# M3.net
KiCad netlist of a schematic drawn in EAGLE
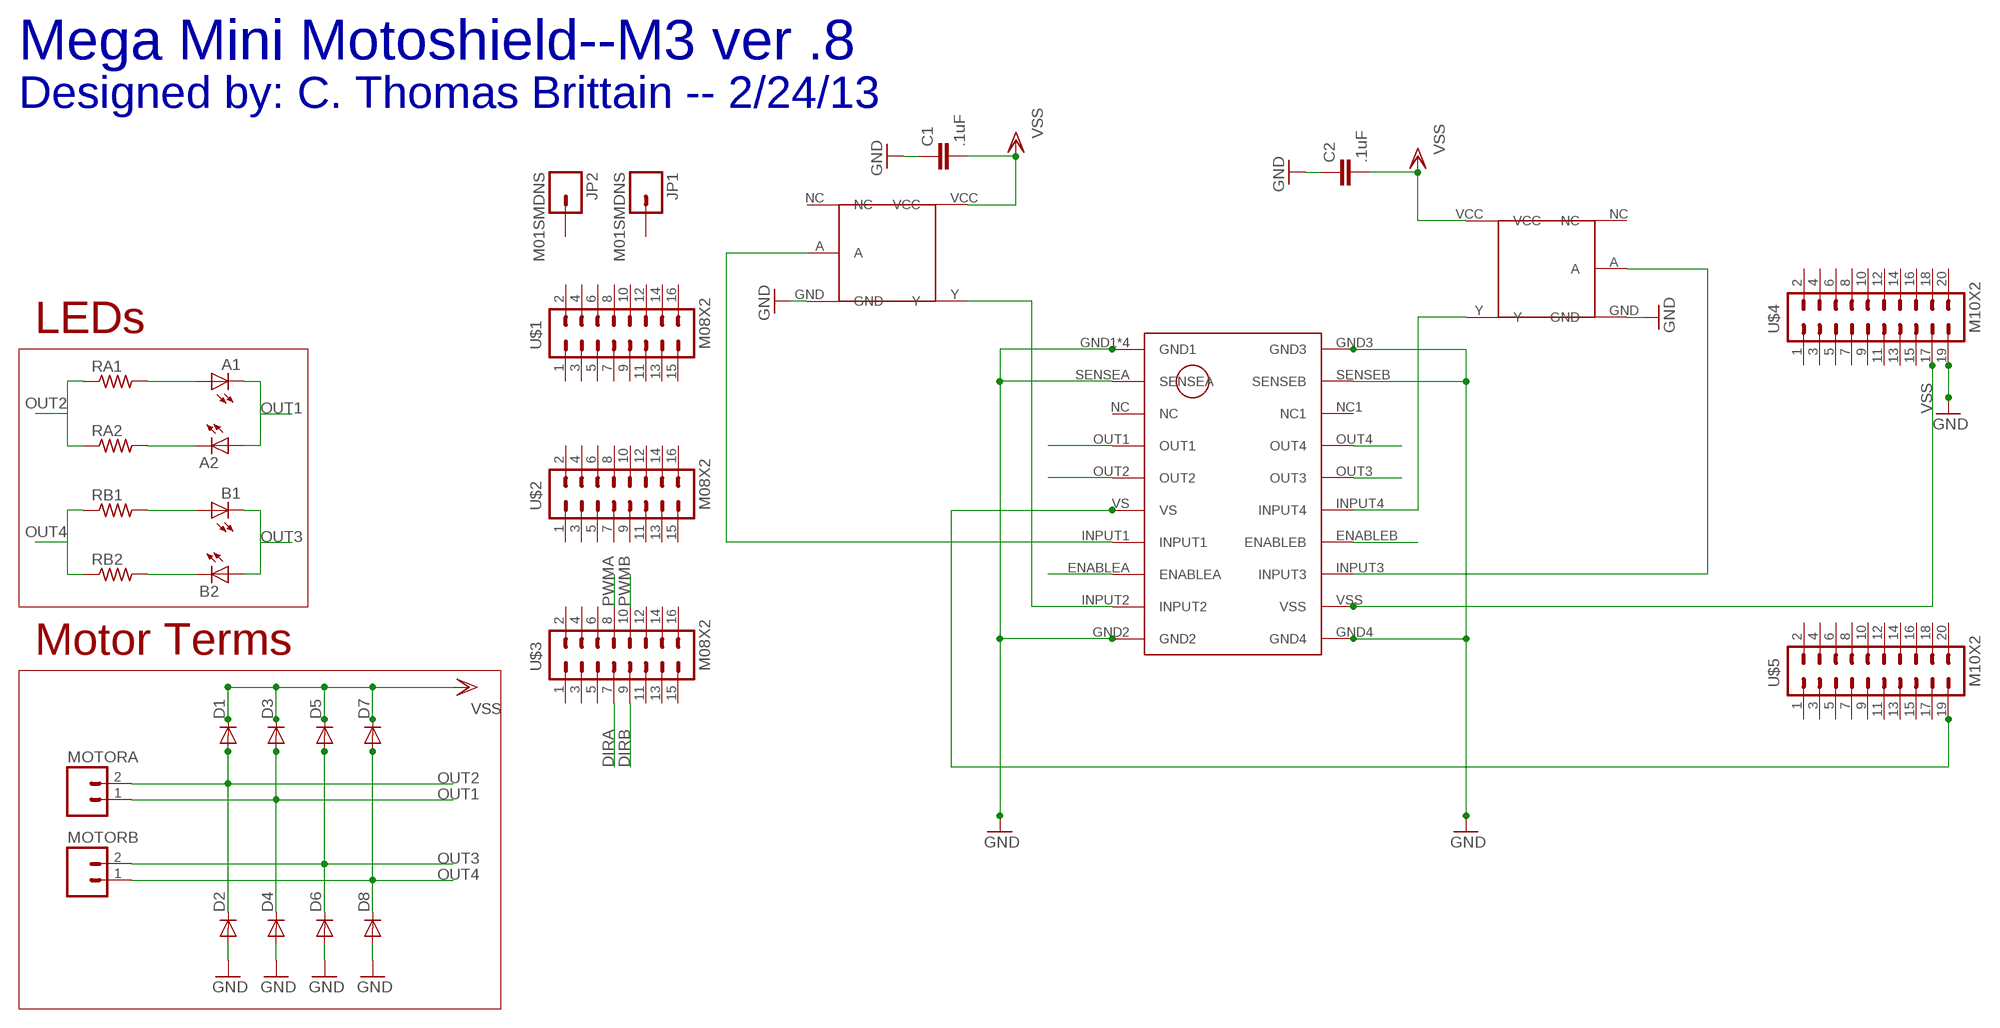
[diagram p0: schematic, sheet 1]

(export (version "E")
  (design (tool "Eeschema 10.0.6"))
  (components
    (comp (ref "A1")
      (value "LEDSML0603")
      (footprint "eagle-import:SML0603")
      (libsource (lib "eagle-import") (part "LEDSML0603"))
    )
    (comp (ref "A2")
      (value "LEDSML0603")
      (footprint "eagle-import:SML0603")
      (libsource (lib "eagle-import") (part "LEDSML0603"))
    )
    (comp (ref "B1")
      (value "LEDSML0603")
      (footprint "eagle-import:SML0603")
      (libsource (lib "eagle-import") (part "LEDSML0603"))
    )
    (comp (ref "B2")
      (value "LEDSML0603")
      (footprint "eagle-import:SML0603")
      (libsource (lib "eagle-import") (part "LEDSML0603"))
    )
    (comp (ref "C1")
      (value ".1uF")
      (footprint "eagle-import:C0805")
      (libsource (lib "eagle-import") (part "C-EUC0805"))
    )
    (comp (ref "C2")
      (value ".1uF")
      (footprint "eagle-import:C0805")
      (libsource (lib "eagle-import") (part "C-EUC0805"))
    )
    (comp (ref "D1")
      (value "DIODESMA")
      (footprint "eagle-import:SMA-DIODE")
      (libsource (lib "eagle-import") (part "DIODESMA"))
    )
    (comp (ref "D2")
      (value "DIODESMA")
      (footprint "eagle-import:SMA-DIODE")
      (libsource (lib "eagle-import") (part "DIODESMA"))
    )
    (comp (ref "D3")
      (value "DIODESMA")
      (footprint "eagle-import:SMA-DIODE")
      (libsource (lib "eagle-import") (part "DIODESMA"))
    )
    (comp (ref "D4")
      (value "DIODESMA")
      (footprint "eagle-import:SMA-DIODE")
      (libsource (lib "eagle-import") (part "DIODESMA"))
    )
    (comp (ref "D5")
      (value "DIODESMA")
      (footprint "eagle-import:SMA-DIODE")
      (libsource (lib "eagle-import") (part "DIODESMA"))
    )
    (comp (ref "D6")
      (value "DIODESMA")
      (footprint "eagle-import:SMA-DIODE")
      (libsource (lib "eagle-import") (part "DIODESMA"))
    )
    (comp (ref "D7")
      (value "DIODESMA")
      (footprint "eagle-import:SMA-DIODE")
      (libsource (lib "eagle-import") (part "DIODESMA"))
    )
    (comp (ref "D8")
      (value "DIODESMA")
      (footprint "eagle-import:SMA-DIODE")
      (libsource (lib "eagle-import") (part "DIODESMA"))
    )
    (comp (ref "JP1")
      (value "M01SMDNS")
      (footprint "eagle-import:1X01NS")
      (libsource (lib "eagle-import") (part "M01SMDNS"))
    )
    (comp (ref "JP2")
      (value "M01SMDNS")
      (footprint "eagle-import:1X01NS")
      (libsource (lib "eagle-import") (part "M01SMDNS"))
    )
    (comp (ref "MOTORA")
      (value "M023.5MM")
      (footprint "eagle-import:SCREWTERMINAL-3.5MM-2")
      (libsource (lib "eagle-import") (part "M023.5MM"))
    )
    (comp (ref "MOTORB")
      (value "M023.5MM")
      (footprint "eagle-import:SCREWTERMINAL-3.5MM-2")
      (libsource (lib "eagle-import") (part "M023.5MM"))
    )
    (comp (ref "RA1")
      (value "R-US_R0805")
      (footprint "eagle-import:R0805")
      (libsource (lib "eagle-import") (part "R-US_R0805"))
    )
    (comp (ref "RA2")
      (value "R-US_R0805")
      (footprint "eagle-import:R0805")
      (libsource (lib "eagle-import") (part "R-US_R0805"))
    )
    (comp (ref "RB1")
      (value "R-US_R0805")
      (footprint "eagle-import:R0805")
      (libsource (lib "eagle-import") (part "R-US_R0805"))
    )
    (comp (ref "RB2")
      (value "R-US_R0805")
      (footprint "eagle-import:R0805")
      (libsource (lib "eagle-import") (part "R-US_R0805"))
    )
    (comp (ref "U$1")
      (value "M08X2")
      (footprint "eagle-import:2X8")
      (libsource (lib "eagle-import") (part "M08X2"))
    )
    (comp (ref "U$2")
      (value "M08X2")
      (footprint "eagle-import:2X8")
      (libsource (lib "eagle-import") (part "M08X2"))
    )
    (comp (ref "U$3")
      (value "M08X2")
      (footprint "eagle-import:2X8")
      (libsource (lib "eagle-import") (part "M08X2"))
    )
    (comp (ref "U$4")
      (value "M10X2")
      (footprint "eagle-import:2X10")
      (libsource (lib "eagle-import") (part "M10X2"))
    )
    (comp (ref "U$5")
      (value "M10X2")
      (footprint "eagle-import:2X10")
      (libsource (lib "eagle-import") (part "M10X2"))
    )
    (comp (ref "U$6")
      (value "L298P")
      (footprint "eagle-import:SMARTPRJ_POWER-SO20")
      (libsource (lib "eagle-import") (part "L298P"))
    )
    (comp (ref "U$7")
      (value "74HC1G04")
      (footprint "eagle-import:SPARKFUN_SC70")
      (libsource (lib "eagle-import") (part "74HC1G04"))
    )
    (comp (ref "U$8")
      (value "74HC1G04")
      (footprint "eagle-import:SPARKFUN_SC70")
      (libsource (lib "eagle-import") (part "74HC1G04"))
    )
  )
  (nets
    (net (code "1") (name "/DIRA") (class "Default")
      (node (ref "U$3") (pin "7") (pinfunction "7_7") (pintype "passive"))
      (node (ref "U$6") (pin "INPUT1") (pinfunction "INPUT1_INPUT1") (pintype "bidirectional"))
      (node (ref "U$7") (pin "A") (pinfunction "A_A") (pintype "bidirectional"))
    )
    (net (code "2") (name "/DIRB") (class "Default")
      (node (ref "U$3") (pin "9") (pinfunction "9_9") (pintype "passive"))
      (node (ref "U$6") (pin "INPUT3") (pinfunction "INPUT3_INPUT3") (pintype "bidirectional"))
      (node (ref "U$8") (pin "A") (pinfunction "A_A") (pintype "bidirectional"))
    )
    (net (code "3") (name "/OUT1") (class "Default")
      (node (ref "A1") (pin "C") (pinfunction "C_C") (pintype "passive"))
      (node (ref "A2") (pin "A") (pinfunction "A_A") (pintype "passive"))
      (node (ref "D3") (pin "A") (pinfunction "A_A") (pintype "passive"))
      (node (ref "D4") (pin "C") (pinfunction "C_C") (pintype "passive"))
      (node (ref "MOTORA") (pin "1") (pinfunction "1_1") (pintype "passive"))
      (node (ref "U$6") (pin "OUT1") (pinfunction "OUT1_OUT1") (pintype "bidirectional"))
    )
    (net (code "4") (name "/OUT2") (class "Default")
      (node (ref "D1") (pin "A") (pinfunction "A_A") (pintype "passive"))
      (node (ref "D2") (pin "C") (pinfunction "C_C") (pintype "passive"))
      (node (ref "MOTORA") (pin "2") (pinfunction "2_2") (pintype "passive"))
      (node (ref "RA1") (pin "1") (pinfunction "1_1") (pintype "passive"))
      (node (ref "RA2") (pin "1") (pinfunction "1_1") (pintype "passive"))
      (node (ref "U$6") (pin "OUT2") (pinfunction "OUT2_OUT2") (pintype "bidirectional"))
    )
    (net (code "5") (name "/OUT3") (class "Default")
      (node (ref "B1") (pin "C") (pinfunction "C_C") (pintype "passive"))
      (node (ref "B2") (pin "A") (pinfunction "A_A") (pintype "passive"))
      (node (ref "D5") (pin "A") (pinfunction "A_A") (pintype "passive"))
      (node (ref "D6") (pin "C") (pinfunction "C_C") (pintype "passive"))
      (node (ref "MOTORB") (pin "2") (pinfunction "2_2") (pintype "passive"))
      (node (ref "U$6") (pin "OUT4") (pinfunction "OUT4_OUT4") (pintype "bidirectional"))
    )
    (net (code "6") (name "/OUT4") (class "Default")
      (node (ref "D7") (pin "A") (pinfunction "A_A") (pintype "passive"))
      (node (ref "D8") (pin "C") (pinfunction "C_C") (pintype "passive"))
      (node (ref "MOTORB") (pin "1") (pinfunction "1_1") (pintype "passive"))
      (node (ref "RB1") (pin "1") (pinfunction "1_1") (pintype "passive"))
      (node (ref "RB2") (pin "1") (pinfunction "1_1") (pintype "passive"))
      (node (ref "U$6") (pin "OUT3") (pinfunction "OUT3_OUT3") (pintype "bidirectional"))
    )
    (net (code "7") (name "/PWMA") (class "Default")
      (node (ref "U$3") (pin "8") (pinfunction "8_8") (pintype "passive"))
      (node (ref "U$6") (pin "ENABLEA") (pinfunction "ENABLEA_ENABLEA") (pintype "bidirectional"))
    )
    (net (code "8") (name "/PWMB") (class "Default")
      (node (ref "U$3") (pin "10") (pinfunction "10_10") (pintype "passive"))
      (node (ref "U$6") (pin "ENABLEB") (pinfunction "ENABLEB_ENABLEB") (pintype "bidirectional"))
    )
    (net (code "9") (name "GND") (class "Default")
      (node (ref "C1") (pin "1") (pinfunction "1_1") (pintype "passive"))
      (node (ref "C2") (pin "1") (pinfunction "1_1") (pintype "passive"))
      (node (ref "D2") (pin "A") (pinfunction "A_A") (pintype "passive"))
      (node (ref "D4") (pin "A") (pinfunction "A_A") (pintype "passive"))
      (node (ref "D6") (pin "A") (pinfunction "A_A") (pintype "passive"))
      (node (ref "D8") (pin "A") (pinfunction "A_A") (pintype "passive"))
      (node (ref "U$4") (pin "19") (pinfunction "19_19") (pintype "passive"))
      (node (ref "U$6") (pin "GND1") (pinfunction "GND1_GND1") (pintype "bidirectional"))
      (node (ref "U$6") (pin "GND2") (pinfunction "GND2_GND2") (pintype "bidirectional"))
      (node (ref "U$6") (pin "GND3") (pinfunction "GND3_GND3") (pintype "bidirectional"))
      (node (ref "U$6") (pin "GND4") (pinfunction "GND4_GND4") (pintype "bidirectional"))
      (node (ref "U$6") (pin "GND5") (pinfunction "GND1_GND5") (pintype "bidirectional"))
      (node (ref "U$6") (pin "GND6") (pinfunction "GND1_GND6") (pintype "bidirectional"))
      (node (ref "U$6") (pin "GND7") (pinfunction "GND1_GND7") (pintype "bidirectional"))
      (node (ref "U$6") (pin "SENSEA") (pinfunction "SENSEA_SENSEA") (pintype "bidirectional"))
      (node (ref "U$6") (pin "SENSEB") (pinfunction "SENSEB_SENSEB") (pintype "bidirectional"))
      (node (ref "U$7") (pin "GND") (pinfunction "GND_GND") (pintype "bidirectional"))
      (node (ref "U$8") (pin "GND") (pinfunction "GND_GND") (pintype "bidirectional"))
    )
    (net (code "10") (name "Net-(A1-PadA)") (class "Default")
      (node (ref "A1") (pin "A") (pinfunction "A_A") (pintype "passive"))
      (node (ref "RA1") (pin "2") (pinfunction "2_2") (pintype "passive"))
    )
    (net (code "11") (name "Net-(A2-PadC)") (class "Default")
      (node (ref "A2") (pin "C") (pinfunction "C_C") (pintype "passive"))
      (node (ref "RA2") (pin "2") (pinfunction "2_2") (pintype "passive"))
    )
    (net (code "12") (name "Net-(B1-PadA)") (class "Default")
      (node (ref "B1") (pin "A") (pinfunction "A_A") (pintype "passive"))
      (node (ref "RB1") (pin "2") (pinfunction "2_2") (pintype "passive"))
    )
    (net (code "13") (name "Net-(B2-PadC)") (class "Default")
      (node (ref "B2") (pin "C") (pinfunction "C_C") (pintype "passive"))
      (node (ref "RB2") (pin "2") (pinfunction "2_2") (pintype "passive"))
    )
    (net (code "14") (name "Net-(U$5-Pad19)") (class "Default")
      (node (ref "U$5") (pin "19") (pinfunction "19_19") (pintype "passive"))
      (node (ref "U$6") (pin "VS") (pinfunction "VS_VS") (pintype "bidirectional"))
    )
    (net (code "15") (name "Net-(U$6-PadINPUT2)") (class "Default")
      (node (ref "U$6") (pin "INPUT2") (pinfunction "INPUT2_INPUT2") (pintype "bidirectional"))
      (node (ref "U$7") (pin "Y") (pinfunction "Y_Y") (pintype "bidirectional"))
    )
    (net (code "16") (name "Net-(U$6-PadINPUT4)") (class "Default")
      (node (ref "U$6") (pin "INPUT4") (pinfunction "INPUT4_INPUT4") (pintype "bidirectional"))
      (node (ref "U$8") (pin "Y") (pinfunction "Y_Y") (pintype "bidirectional"))
    )
    (net (code "17") (name "VSS") (class "Default")
      (node (ref "C1") (pin "2") (pinfunction "2_2") (pintype "passive"))
      (node (ref "C2") (pin "2") (pinfunction "2_2") (pintype "passive"))
      (node (ref "D1") (pin "C") (pinfunction "C_C") (pintype "passive"))
      (node (ref "D3") (pin "C") (pinfunction "C_C") (pintype "passive"))
      (node (ref "D5") (pin "C") (pinfunction "C_C") (pintype "passive"))
      (node (ref "D7") (pin "C") (pinfunction "C_C") (pintype "passive"))
      (node (ref "U$4") (pin "17") (pinfunction "17_17") (pintype "passive"))
      (node (ref "U$6") (pin "VSS") (pinfunction "VSS_VSS") (pintype "bidirectional"))
      (node (ref "U$7") (pin "VCC") (pinfunction "VCC_VCC") (pintype "bidirectional"))
      (node (ref "U$8") (pin "VCC") (pinfunction "VCC_VCC") (pintype "bidirectional"))
    )
    (net (code "18") (name "unconnected-(JP1-Pad1)") (class "Default")
      (node (ref "JP1") (pin "1") (pinfunction "1_1") (pintype "passive"))
    )
    (net (code "19") (name "unconnected-(JP2-Pad1)") (class "Default")
      (node (ref "JP2") (pin "1") (pinfunction "1_1") (pintype "passive"))
    )
    (net (code "20") (name "unconnected-(U$1-Pad1)") (class "Default")
      (node (ref "U$1") (pin "1") (pinfunction "1_1") (pintype "passive"))
    )
    (net (code "21") (name "unconnected-(U$1-Pad2)") (class "Default")
      (node (ref "U$1") (pin "2") (pinfunction "2_2") (pintype "passive"))
    )
    (net (code "22") (name "unconnected-(U$1-Pad3)") (class "Default")
      (node (ref "U$1") (pin "3") (pinfunction "3_3") (pintype "passive"))
    )
    (net (code "23") (name "unconnected-(U$1-Pad4)") (class "Default")
      (node (ref "U$1") (pin "4") (pinfunction "4_4") (pintype "passive"))
    )
    (net (code "24") (name "unconnected-(U$1-Pad5)") (class "Default")
      (node (ref "U$1") (pin "5") (pinfunction "5_5") (pintype "passive"))
    )
    (net (code "25") (name "unconnected-(U$1-Pad6)") (class "Default")
      (node (ref "U$1") (pin "6") (pinfunction "6_6") (pintype "passive"))
    )
    (net (code "26") (name "unconnected-(U$1-Pad7)") (class "Default")
      (node (ref "U$1") (pin "7") (pinfunction "7_7") (pintype "passive"))
    )
    (net (code "27") (name "unconnected-(U$1-Pad8)") (class "Default")
      (node (ref "U$1") (pin "8") (pinfunction "8_8") (pintype "passive"))
    )
    (net (code "28") (name "unconnected-(U$1-Pad9)") (class "Default")
      (node (ref "U$1") (pin "9") (pinfunction "9_9") (pintype "passive"))
    )
    (net (code "29") (name "unconnected-(U$1-Pad10)") (class "Default")
      (node (ref "U$1") (pin "10") (pinfunction "10_10") (pintype "passive"))
    )
    (net (code "30") (name "unconnected-(U$1-Pad11)") (class "Default")
      (node (ref "U$1") (pin "11") (pinfunction "11_11") (pintype "passive"))
    )
    (net (code "31") (name "unconnected-(U$1-Pad12)") (class "Default")
      (node (ref "U$1") (pin "12") (pinfunction "12_12") (pintype "passive"))
    )
    (net (code "32") (name "unconnected-(U$1-Pad13)") (class "Default")
      (node (ref "U$1") (pin "13") (pinfunction "13_13") (pintype "passive"))
    )
    (net (code "33") (name "unconnected-(U$1-Pad14)") (class "Default")
      (node (ref "U$1") (pin "14") (pinfunction "14_14") (pintype "passive"))
    )
    (net (code "34") (name "unconnected-(U$1-Pad15)") (class "Default")
      (node (ref "U$1") (pin "15") (pinfunction "15_15") (pintype "passive"))
    )
    (net (code "35") (name "unconnected-(U$1-Pad16)") (class "Default")
      (node (ref "U$1") (pin "16") (pinfunction "16_16") (pintype "passive"))
    )
    (net (code "36") (name "unconnected-(U$2-Pad1)") (class "Default")
      (node (ref "U$2") (pin "1") (pinfunction "1_1") (pintype "passive"))
    )
    (net (code "37") (name "unconnected-(U$2-Pad2)") (class "Default")
      (node (ref "U$2") (pin "2") (pinfunction "2_2") (pintype "passive"))
    )
    (net (code "38") (name "unconnected-(U$2-Pad3)") (class "Default")
      (node (ref "U$2") (pin "3") (pinfunction "3_3") (pintype "passive"))
    )
    (net (code "39") (name "unconnected-(U$2-Pad4)") (class "Default")
      (node (ref "U$2") (pin "4") (pinfunction "4_4") (pintype "passive"))
    )
    (net (code "40") (name "unconnected-(U$2-Pad5)") (class "Default")
      (node (ref "U$2") (pin "5") (pinfunction "5_5") (pintype "passive"))
    )
    (net (code "41") (name "unconnected-(U$2-Pad6)") (class "Default")
      (node (ref "U$2") (pin "6") (pinfunction "6_6") (pintype "passive"))
    )
    (net (code "42") (name "unconnected-(U$2-Pad7)") (class "Default")
      (node (ref "U$2") (pin "7") (pinfunction "7_7") (pintype "passive"))
    )
    (net (code "43") (name "unconnected-(U$2-Pad8)") (class "Default")
      (node (ref "U$2") (pin "8") (pinfunction "8_8") (pintype "passive"))
    )
    (net (code "44") (name "unconnected-(U$2-Pad9)") (class "Default")
      (node (ref "U$2") (pin "9") (pinfunction "9_9") (pintype "passive"))
    )
    (net (code "45") (name "unconnected-(U$2-Pad10)") (class "Default")
      (node (ref "U$2") (pin "10") (pinfunction "10_10") (pintype "passive"))
    )
    (net (code "46") (name "unconnected-(U$2-Pad11)") (class "Default")
      (node (ref "U$2") (pin "11") (pinfunction "11_11") (pintype "passive"))
    )
    (net (code "47") (name "unconnected-(U$2-Pad12)") (class "Default")
      (node (ref "U$2") (pin "12") (pinfunction "12_12") (pintype "passive"))
    )
    (net (code "48") (name "unconnected-(U$2-Pad13)") (class "Default")
      (node (ref "U$2") (pin "13") (pinfunction "13_13") (pintype "passive"))
    )
    (net (code "49") (name "unconnected-(U$2-Pad14)") (class "Default")
      (node (ref "U$2") (pin "14") (pinfunction "14_14") (pintype "passive"))
    )
    (net (code "50") (name "unconnected-(U$2-Pad15)") (class "Default")
      (node (ref "U$2") (pin "15") (pinfunction "15_15") (pintype "passive"))
    )
    (net (code "51") (name "unconnected-(U$2-Pad16)") (class "Default")
      (node (ref "U$2") (pin "16") (pinfunction "16_16") (pintype "passive"))
    )
    (net (code "52") (name "unconnected-(U$3-Pad1)") (class "Default")
      (node (ref "U$3") (pin "1") (pinfunction "1_1") (pintype "passive"))
    )
    (net (code "53") (name "unconnected-(U$3-Pad2)") (class "Default")
      (node (ref "U$3") (pin "2") (pinfunction "2_2") (pintype "passive"))
    )
    (net (code "54") (name "unconnected-(U$3-Pad3)") (class "Default")
      (node (ref "U$3") (pin "3") (pinfunction "3_3") (pintype "passive"))
    )
    (net (code "55") (name "unconnected-(U$3-Pad4)") (class "Default")
      (node (ref "U$3") (pin "4") (pinfunction "4_4") (pintype "passive"))
    )
    (net (code "56") (name "unconnected-(U$3-Pad5)") (class "Default")
      (node (ref "U$3") (pin "5") (pinfunction "5_5") (pintype "passive"))
    )
    (net (code "57") (name "unconnected-(U$3-Pad6)") (class "Default")
      (node (ref "U$3") (pin "6") (pinfunction "6_6") (pintype "passive"))
    )
    (net (code "58") (name "unconnected-(U$3-Pad11)") (class "Default")
      (node (ref "U$3") (pin "11") (pinfunction "11_11") (pintype "passive"))
    )
    (net (code "59") (name "unconnected-(U$3-Pad12)") (class "Default")
      (node (ref "U$3") (pin "12") (pinfunction "12_12") (pintype "passive"))
    )
    (net (code "60") (name "unconnected-(U$3-Pad13)") (class "Default")
      (node (ref "U$3") (pin "13") (pinfunction "13_13") (pintype "passive"))
    )
    (net (code "61") (name "unconnected-(U$3-Pad14)") (class "Default")
      (node (ref "U$3") (pin "14") (pinfunction "14_14") (pintype "passive"))
    )
    (net (code "62") (name "unconnected-(U$3-Pad15)") (class "Default")
      (node (ref "U$3") (pin "15") (pinfunction "15_15") (pintype "passive"))
    )
    (net (code "63") (name "unconnected-(U$3-Pad16)") (class "Default")
      (node (ref "U$3") (pin "16") (pinfunction "16_16") (pintype "passive"))
    )
    (net (code "64") (name "unconnected-(U$4-Pad1)") (class "Default")
      (node (ref "U$4") (pin "1") (pinfunction "1_1") (pintype "passive"))
    )
    (net (code "65") (name "unconnected-(U$4-Pad2)") (class "Default")
      (node (ref "U$4") (pin "2") (pinfunction "2_2") (pintype "passive"))
    )
    (net (code "66") (name "unconnected-(U$4-Pad3)") (class "Default")
      (node (ref "U$4") (pin "3") (pinfunction "3_3") (pintype "passive"))
    )
    (net (code "67") (name "unconnected-(U$4-Pad4)") (class "Default")
      (node (ref "U$4") (pin "4") (pinfunction "4_4") (pintype "passive"))
    )
    (net (code "68") (name "unconnected-(U$4-Pad5)") (class "Default")
      (node (ref "U$4") (pin "5") (pinfunction "5_5") (pintype "passive"))
    )
    (net (code "69") (name "unconnected-(U$4-Pad6)") (class "Default")
      (node (ref "U$4") (pin "6") (pinfunction "6_6") (pintype "passive"))
    )
    (net (code "70") (name "unconnected-(U$4-Pad7)") (class "Default")
      (node (ref "U$4") (pin "7") (pinfunction "7_7") (pintype "passive"))
    )
    (net (code "71") (name "unconnected-(U$4-Pad8)") (class "Default")
      (node (ref "U$4") (pin "8") (pinfunction "8_8") (pintype "passive"))
    )
    (net (code "72") (name "unconnected-(U$4-Pad9)") (class "Default")
      (node (ref "U$4") (pin "9") (pinfunction "9_9") (pintype "passive"))
    )
    (net (code "73") (name "unconnected-(U$4-Pad10)") (class "Default")
      (node (ref "U$4") (pin "10") (pinfunction "10_10") (pintype "passive"))
    )
    (net (code "74") (name "unconnected-(U$4-Pad11)") (class "Default")
      (node (ref "U$4") (pin "11") (pinfunction "11_11") (pintype "passive"))
    )
    (net (code "75") (name "unconnected-(U$4-Pad12)") (class "Default")
      (node (ref "U$4") (pin "12") (pinfunction "12_12") (pintype "passive"))
    )
    (net (code "76") (name "unconnected-(U$4-Pad13)") (class "Default")
      (node (ref "U$4") (pin "13") (pinfunction "13_13") (pintype "passive"))
    )
    (net (code "77") (name "unconnected-(U$4-Pad14)") (class "Default")
      (node (ref "U$4") (pin "14") (pinfunction "14_14") (pintype "passive"))
    )
    (net (code "78") (name "unconnected-(U$4-Pad15)") (class "Default")
      (node (ref "U$4") (pin "15") (pinfunction "15_15") (pintype "passive"))
    )
    (net (code "79") (name "unconnected-(U$4-Pad16)") (class "Default")
      (node (ref "U$4") (pin "16") (pinfunction "16_16") (pintype "passive"))
    )
    (net (code "80") (name "unconnected-(U$4-Pad18)") (class "Default")
      (node (ref "U$4") (pin "18") (pinfunction "18_18") (pintype "passive"))
    )
    (net (code "81") (name "unconnected-(U$4-Pad20)") (class "Default")
      (node (ref "U$4") (pin "20") (pinfunction "20_20") (pintype "passive"))
    )
    (net (code "82") (name "unconnected-(U$5-Pad1)") (class "Default")
      (node (ref "U$5") (pin "1") (pinfunction "1_1") (pintype "passive"))
    )
    (net (code "83") (name "unconnected-(U$5-Pad2)") (class "Default")
      (node (ref "U$5") (pin "2") (pinfunction "2_2") (pintype "passive"))
    )
    (net (code "84") (name "unconnected-(U$5-Pad3)") (class "Default")
      (node (ref "U$5") (pin "3") (pinfunction "3_3") (pintype "passive"))
    )
    (net (code "85") (name "unconnected-(U$5-Pad4)") (class "Default")
      (node (ref "U$5") (pin "4") (pinfunction "4_4") (pintype "passive"))
    )
    (net (code "86") (name "unconnected-(U$5-Pad5)") (class "Default")
      (node (ref "U$5") (pin "5") (pinfunction "5_5") (pintype "passive"))
    )
    (net (code "87") (name "unconnected-(U$5-Pad6)") (class "Default")
      (node (ref "U$5") (pin "6") (pinfunction "6_6") (pintype "passive"))
    )
    (net (code "88") (name "unconnected-(U$5-Pad7)") (class "Default")
      (node (ref "U$5") (pin "7") (pinfunction "7_7") (pintype "passive"))
    )
    (net (code "89") (name "unconnected-(U$5-Pad8)") (class "Default")
      (node (ref "U$5") (pin "8") (pinfunction "8_8") (pintype "passive"))
    )
    (net (code "90") (name "unconnected-(U$5-Pad9)") (class "Default")
      (node (ref "U$5") (pin "9") (pinfunction "9_9") (pintype "passive"))
    )
    (net (code "91") (name "unconnected-(U$5-Pad10)") (class "Default")
      (node (ref "U$5") (pin "10") (pinfunction "10_10") (pintype "passive"))
    )
    (net (code "92") (name "unconnected-(U$5-Pad11)") (class "Default")
      (node (ref "U$5") (pin "11") (pinfunction "11_11") (pintype "passive"))
    )
    (net (code "93") (name "unconnected-(U$5-Pad12)") (class "Default")
      (node (ref "U$5") (pin "12") (pinfunction "12_12") (pintype "passive"))
    )
    (net (code "94") (name "unconnected-(U$5-Pad13)") (class "Default")
      (node (ref "U$5") (pin "13") (pinfunction "13_13") (pintype "passive"))
    )
    (net (code "95") (name "unconnected-(U$5-Pad14)") (class "Default")
      (node (ref "U$5") (pin "14") (pinfunction "14_14") (pintype "passive"))
    )
    (net (code "96") (name "unconnected-(U$5-Pad15)") (class "Default")
      (node (ref "U$5") (pin "15") (pinfunction "15_15") (pintype "passive"))
    )
    (net (code "97") (name "unconnected-(U$5-Pad16)") (class "Default")
      (node (ref "U$5") (pin "16") (pinfunction "16_16") (pintype "passive"))
    )
    (net (code "98") (name "unconnected-(U$5-Pad17)") (class "Default")
      (node (ref "U$5") (pin "17") (pinfunction "17_17") (pintype "passive"))
    )
    (net (code "99") (name "unconnected-(U$5-Pad18)") (class "Default")
      (node (ref "U$5") (pin "18") (pinfunction "18_18") (pintype "passive"))
    )
    (net (code "100") (name "unconnected-(U$5-Pad20)") (class "Default")
      (node (ref "U$5") (pin "20") (pinfunction "20_20") (pintype "passive"))
    )
    (net (code "101") (name "unconnected-(U$6-PadNC)") (class "Default")
      (node (ref "U$6") (pin "NC") (pinfunction "NC_NC") (pintype "bidirectional"))
    )
    (net (code "102") (name "unconnected-(U$6-PadNC1)") (class "Default")
      (node (ref "U$6") (pin "NC1") (pinfunction "NC1_NC1") (pintype "bidirectional"))
    )
    (net (code "103") (name "unconnected-(U$7-PadNC)") (class "Default")
      (node (ref "U$7") (pin "NC") (pinfunction "NC_NC") (pintype "bidirectional"))
    )
    (net (code "104") (name "unconnected-(U$8-PadNC)") (class "Default")
      (node (ref "U$8") (pin "NC") (pinfunction "NC_NC") (pintype "bidirectional"))
    )
  )
)
